# Puzzle-EMG_Sensor_v1_0.net
KiCad netlist of a schematic drawn in EAGLE
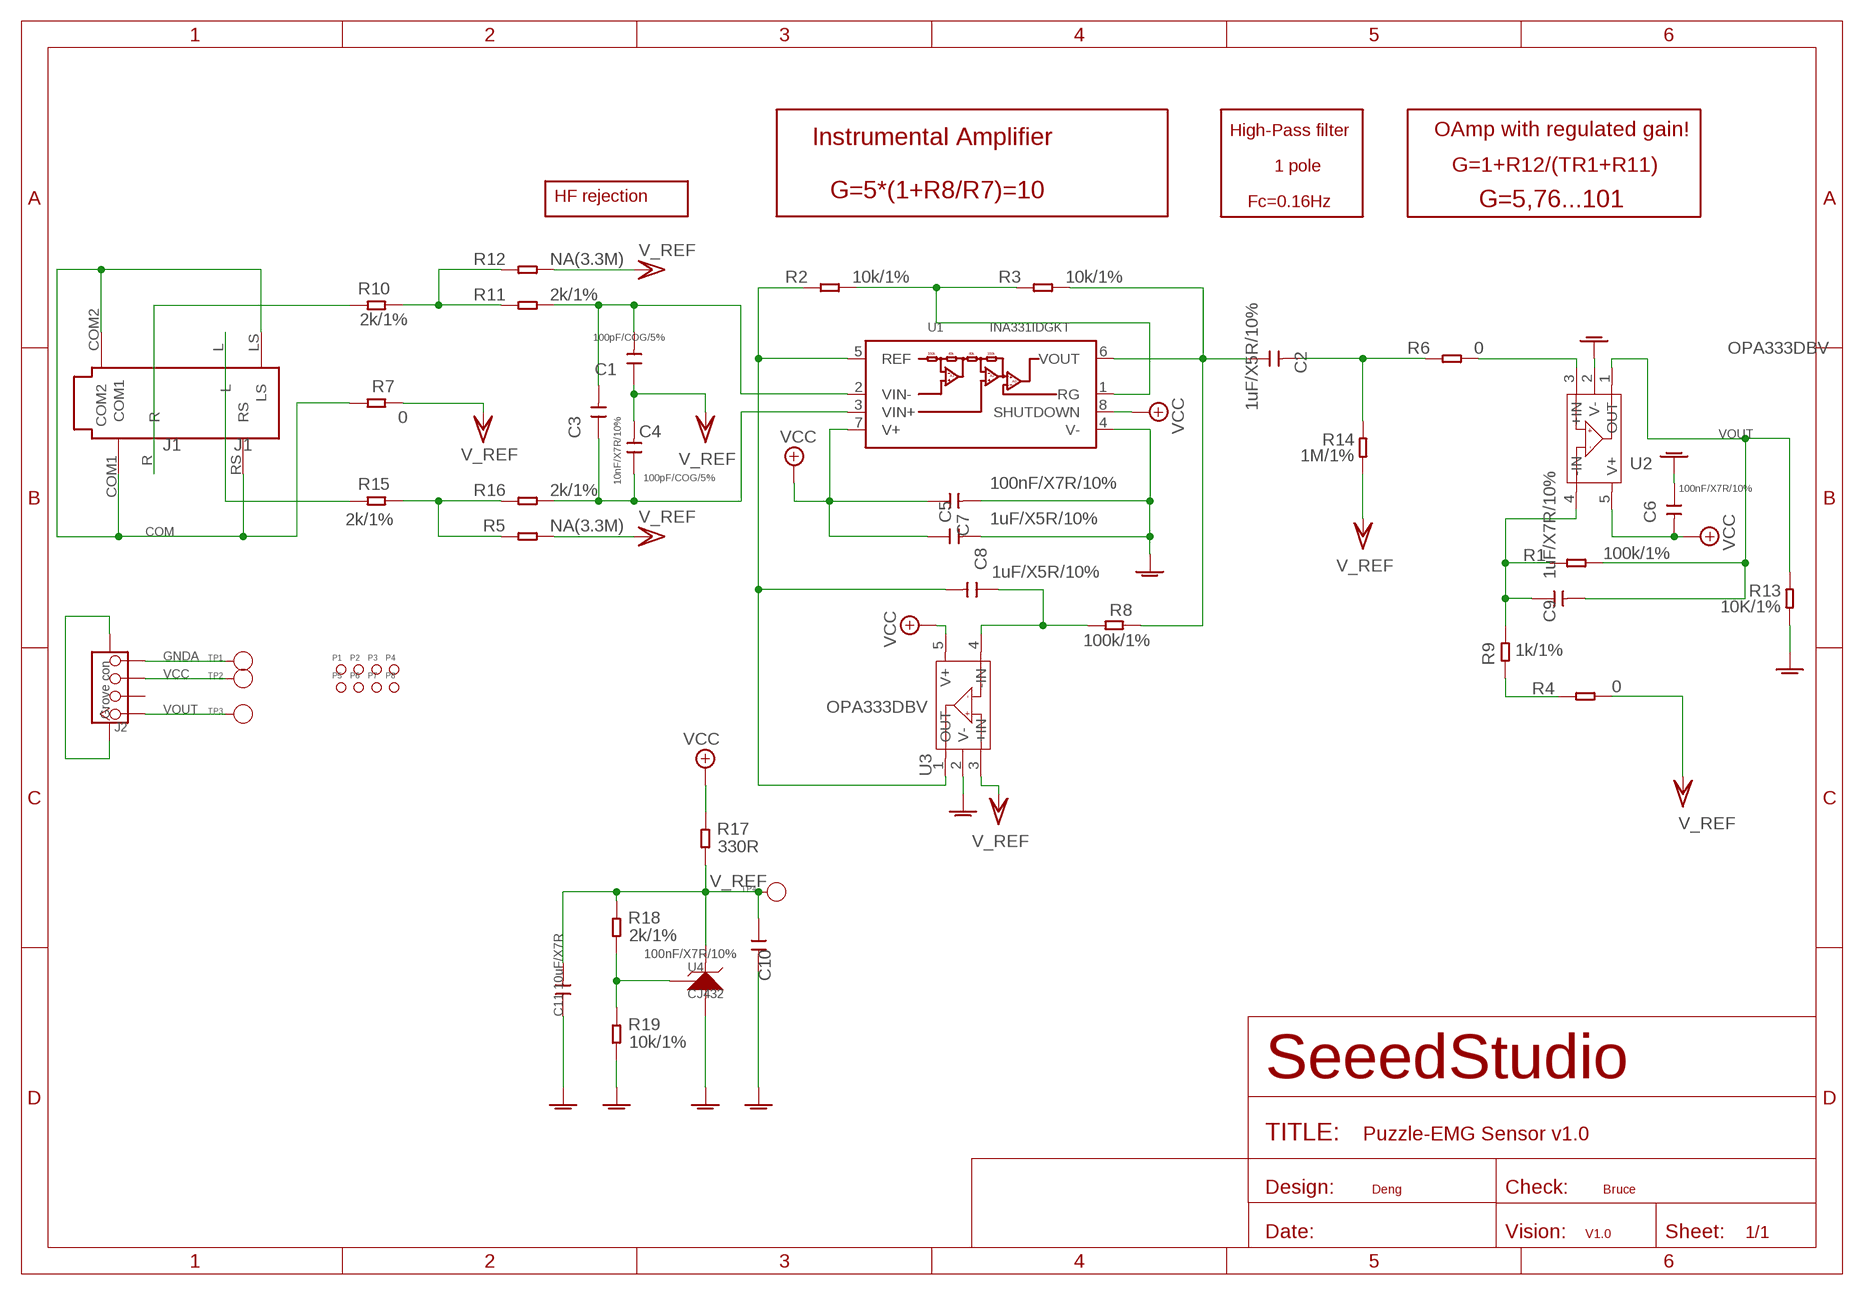
[diagram p0: schematic, sheet 1]

(export (version "E")
  (design (tool "Eeschema 10.0.6"))
  (components
    (comp (ref "C1")
      (value "100pF/COG/5%")
      (footprint "eagle-import:C0603")
      (libsource (lib "eagle-import") (part "C-0603"))
    )
    (comp (ref "C2")
      (value "1uF/X5R/10%")
      (footprint "eagle-import:C0603")
      (libsource (lib "eagle-import") (part "C-0603"))
    )
    (comp (ref "C3")
      (value "10nF/X7R/10%")
      (footprint "eagle-import:C0603")
      (libsource (lib "eagle-import") (part "C-0603"))
    )
    (comp (ref "C4")
      (value "100pF/COG/5%")
      (footprint "eagle-import:C0603")
      (libsource (lib "eagle-import") (part "C-0603"))
    )
    (comp (ref "C5")
      (value "100nF/X7R/10%")
      (footprint "eagle-import:C0603")
      (libsource (lib "eagle-import") (part "C-0603"))
    )
    (comp (ref "C6")
      (value "100nF/X7R/10%")
      (footprint "eagle-import:C0603")
      (libsource (lib "eagle-import") (part "C-0603"))
    )
    (comp (ref "C7")
      (value "1uF/X5R/10%")
      (footprint "eagle-import:C0603")
      (libsource (lib "eagle-import") (part "C-0603"))
    )
    (comp (ref "C8")
      (value "1uF/X5R/10%")
      (footprint "eagle-import:C0603")
      (libsource (lib "eagle-import") (part "C-0603"))
    )
    (comp (ref "C9")
      (value "1uF/X7R/10%")
      (footprint "eagle-import:C0603")
      (libsource (lib "eagle-import") (part "C-0603"))
    )
    (comp (ref "C10")
      (value "100nF/X7R/10%")
      (footprint "eagle-import:C0603")
      (libsource (lib "eagle-import") (part "C-0603"))
    )
    (comp (ref "C11")
      (value "10uF/X7R")
      (footprint "eagle-import:C0805")
      (libsource (lib "eagle-import") (part "C-0805"))
    )
    (comp (ref "J1")
      (value "J1")
      (footprint "eagle-import:6P-SMD-3.5-NEW")
      (libsource (lib "eagle-import") (part "AUDIO-6P-SMD"))
    )
    (comp (ref "J2")
      (value "Grove con")
      (footprint "eagle-import:4P-SMD-2.0")
      (libsource (lib "eagle-import") (part "TWIG-4P-2.0-SMD-FEMALE-REINFORCE'DD'"))
    )
    (comp (ref "P1")
      (value "PAD-MARK")
      (footprint "eagle-import:ROUND-MARK-1.0")
      (fields (field (name "PARTNO") "DNP"))
      (libsource (lib "eagle-import") (part "PAD-MARK"))
    )
    (comp (ref "P2")
      (value "PAD-MARK")
      (footprint "eagle-import:ROUND-MARK-1.0")
      (fields (field (name "PARTNO") "DNP"))
      (libsource (lib "eagle-import") (part "PAD-MARK"))
    )
    (comp (ref "P3")
      (value "PAD-MARK")
      (footprint "eagle-import:ROUND-MARK-1.0")
      (fields (field (name "PARTNO") "DNP"))
      (libsource (lib "eagle-import") (part "PAD-MARK"))
    )
    (comp (ref "P4")
      (value "PAD-MARK")
      (footprint "eagle-import:ROUND-MARK-1.0")
      (fields (field (name "PARTNO") "DNP"))
      (libsource (lib "eagle-import") (part "PAD-MARK"))
    )
    (comp (ref "P5")
      (value "PAD-MARK")
      (footprint "eagle-import:ROUND-MARK-1.0")
      (fields (field (name "PARTNO") "DNP"))
      (libsource (lib "eagle-import") (part "PAD-MARK"))
    )
    (comp (ref "P6")
      (value "PAD-MARK")
      (footprint "eagle-import:ROUND-MARK-1.0")
      (fields (field (name "PARTNO") "DNP"))
      (libsource (lib "eagle-import") (part "PAD-MARK"))
    )
    (comp (ref "P7")
      (value "PAD-MARK")
      (footprint "eagle-import:ROUND-MARK-1.0")
      (fields (field (name "PARTNO") "DNP"))
      (libsource (lib "eagle-import") (part "PAD-MARK"))
    )
    (comp (ref "P8")
      (value "PAD-MARK")
      (footprint "eagle-import:ROUND-MARK-1.0")
      (fields (field (name "PARTNO") "DNP"))
      (libsource (lib "eagle-import") (part "PAD-MARK"))
    )
    (comp (ref "R1")
      (value "100k/1%")
      (footprint "eagle-import:R0603")
      (libsource (lib "eagle-import") (part "R-0603"))
    )
    (comp (ref "R2")
      (value "10k/1%")
      (footprint "eagle-import:R0603")
      (libsource (lib "eagle-import") (part "R-0603"))
    )
    (comp (ref "R3")
      (value "10k/1%")
      (footprint "eagle-import:R0603")
      (libsource (lib "eagle-import") (part "R-0603"))
    )
    (comp (ref "R4")
      (value "0")
      (footprint "eagle-import:R0603")
      (libsource (lib "eagle-import") (part "R-0603"))
    )
    (comp (ref "R5")
      (value "NA(3.3M)")
      (footprint "eagle-import:R0603")
      (libsource (lib "eagle-import") (part "R-0603"))
    )
    (comp (ref "R6")
      (value "0")
      (footprint "eagle-import:R0603")
      (libsource (lib "eagle-import") (part "R-0603"))
    )
    (comp (ref "R7")
      (value "0")
      (footprint "eagle-import:R0603")
      (libsource (lib "eagle-import") (part "R-0603"))
    )
    (comp (ref "R8")
      (value "100k/1%")
      (footprint "eagle-import:R0603")
      (libsource (lib "eagle-import") (part "R-0603"))
    )
    (comp (ref "R9")
      (value "1k/1%")
      (footprint "eagle-import:R0603")
      (libsource (lib "eagle-import") (part "R-0603"))
    )
    (comp (ref "R10")
      (value "2k/1%")
      (footprint "eagle-import:R0603")
      (libsource (lib "eagle-import") (part "R-0603"))
    )
    (comp (ref "R11")
      (value "2k/1%")
      (footprint "eagle-import:R0603")
      (libsource (lib "eagle-import") (part "R-0603"))
    )
    (comp (ref "R12")
      (value "NA(3.3M)")
      (footprint "eagle-import:R0603")
      (libsource (lib "eagle-import") (part "R-0603"))
    )
    (comp (ref "R13")
      (value "10K/1%")
      (footprint "eagle-import:R0603")
      (libsource (lib "eagle-import") (part "R-0603"))
    )
    (comp (ref "R14")
      (value "1M/1%")
      (footprint "eagle-import:R0603")
      (libsource (lib "eagle-import") (part "R-0603"))
    )
    (comp (ref "R15")
      (value "2k/1%")
      (footprint "eagle-import:R0603")
      (libsource (lib "eagle-import") (part "R-0603"))
    )
    (comp (ref "R16")
      (value "2k/1%")
      (footprint "eagle-import:R0603")
      (libsource (lib "eagle-import") (part "R-0603"))
    )
    (comp (ref "R17")
      (value "330R")
      (footprint "eagle-import:R0603")
      (libsource (lib "eagle-import") (part "R-0603"))
    )
    (comp (ref "R18")
      (value "2k/1%")
      (footprint "eagle-import:R0603")
      (libsource (lib "eagle-import") (part "R-0603"))
    )
    (comp (ref "R19")
      (value "10k/1%")
      (footprint "eagle-import:R0603")
      (libsource (lib "eagle-import") (part "R-0603"))
    )
    (comp (ref "TP1")
      (value "TP1")
      (footprint "eagle-import:TP_4545")
      (fields (field (name "PARTNO") "DNP"))
      (libsource (lib "eagle-import") (part "PAD-TEST-POINT'4545'"))
    )
    (comp (ref "TP2")
      (value "TP2")
      (footprint "eagle-import:TP_4545")
      (fields (field (name "PARTNO") "DNP"))
      (libsource (lib "eagle-import") (part "PAD-TEST-POINT'4545'"))
    )
    (comp (ref "TP3")
      (value "TP3")
      (footprint "eagle-import:TP_4545")
      (fields (field (name "PARTNO") "DNP"))
      (libsource (lib "eagle-import") (part "PAD-TEST-POINT'4545'"))
    )
    (comp (ref "TP4")
      (value "TP4")
      (footprint "eagle-import:TP_4545")
      (fields (field (name "PARTNO") "DNP"))
      (libsource (lib "eagle-import") (part "PAD-TEST-POINT'4545'"))
    )
    (comp (ref "U1")
      (value "INA331IDGKT")
      (footprint "eagle-import:MSOP-8")
      (libsource (lib "eagle-import") (part "INA331EA"))
    )
    (comp (ref "U2")
      (value "OPA333DBV")
      (footprint "eagle-import:SOT23-5")
      (libsource (lib "eagle-import") (part "OPA333DBV"))
    )
    (comp (ref "U3")
      (value "OPA333DBV")
      (footprint "eagle-import:SOT23-5")
      (libsource (lib "eagle-import") (part "OPA333DBV"))
    )
    (comp (ref "U4")
      (value "CJ432")
      (footprint "eagle-import:SOT23")
      (libsource (lib "eagle-import") (part "REFERENCE-SOURCE"))
    )
  )
  (nets
    (net (code "1") (name "/COM") (class "Default")
      (node (ref "J1") (pin "COM1") (pinfunction "COM1_COM1") (pintype "bidirectional"))
      (node (ref "J1") (pin "COM2") (pinfunction "COM2_COM2") (pintype "bidirectional"))
      (node (ref "J1") (pin "LS") (pinfunction "LS_LS") (pintype "bidirectional"))
      (node (ref "J1") (pin "RS") (pinfunction "RS_RS") (pintype "bidirectional"))
      (node (ref "R7") (pin "1") (pinfunction "1_1") (pintype "passive"))
    )
    (net (code "2") (name "/VOUT") (class "Default")
      (node (ref "C9") (pin "2") (pinfunction "2_2") (pintype "passive"))
      (node (ref "J2") (pin "1") (pinfunction "1_1") (pintype "bidirectional"))
      (node (ref "R1") (pin "2") (pinfunction "2_2") (pintype "passive"))
      (node (ref "R13") (pin "1") (pinfunction "1_1") (pintype "passive"))
      (node (ref "TP3") (pin "T") (pinfunction "T_T") (pintype "bidirectional"))
      (node (ref "U2") (pin "1") (pinfunction "OUT_1") (pintype "bidirectional"))
    )
    (net (code "3") (name "GNDA") (class "Default")
      (node (ref "C10") (pin "2") (pinfunction "2_2") (pintype "passive"))
      (node (ref "C11") (pin "1") (pinfunction "1_1") (pintype "passive"))
      (node (ref "C5") (pin "2") (pinfunction "2_2") (pintype "passive"))
      (node (ref "C6") (pin "1") (pinfunction "1_1") (pintype "passive"))
      (node (ref "C7") (pin "2") (pinfunction "2_2") (pintype "passive"))
      (node (ref "J2") (pin "4") (pinfunction "4_4") (pintype "bidirectional"))
      (node (ref "R13") (pin "2") (pinfunction "2_2") (pintype "passive"))
      (node (ref "R19") (pin "1") (pinfunction "1_1") (pintype "passive"))
      (node (ref "TP1") (pin "T") (pinfunction "T_T") (pintype "bidirectional"))
      (node (ref "U1") (pin "4") (pinfunction "V-_4") (pintype "power_in"))
      (node (ref "U2") (pin "2") (pinfunction "V-_2") (pintype "bidirectional"))
      (node (ref "U3") (pin "2") (pinfunction "V-_2") (pintype "bidirectional"))
      (node (ref "U4") (pin "3") (pinfunction "A_3") (pintype "bidirectional"))
    )
    (net (code "4") (name "Net-(C2-Pad2)") (class "Default")
      (node (ref "C2") (pin "2") (pinfunction "2_2") (pintype "passive"))
      (node (ref "R14") (pin "1") (pinfunction "1_1") (pintype "passive"))
      (node (ref "R6") (pin "2") (pinfunction "2_2") (pintype "passive"))
    )
    (net (code "5") (name "Net-(J1-PadL)") (class "Default")
      (node (ref "J1") (pin "L") (pinfunction "L_L") (pintype "bidirectional"))
      (node (ref "R15") (pin "1") (pinfunction "1_1") (pintype "passive"))
    )
    (net (code "6") (name "Net-(J1-PadR)") (class "Default")
      (node (ref "J1") (pin "R") (pinfunction "R_R") (pintype "bidirectional"))
      (node (ref "R10") (pin "1") (pinfunction "1_1") (pintype "passive"))
    )
    (net (code "7") (name "Net-(R4-Pad1)") (class "Default")
      (node (ref "R4") (pin "1") (pinfunction "1_1") (pintype "passive"))
      (node (ref "R9") (pin "2") (pinfunction "2_2") (pintype "passive"))
    )
    (net (code "8") (name "Net-(R10-Pad2)") (class "Default")
      (node (ref "R10") (pin "2") (pinfunction "2_2") (pintype "passive"))
      (node (ref "R11") (pin "2") (pinfunction "2_2") (pintype "passive"))
      (node (ref "R12") (pin "2") (pinfunction "2_2") (pintype "passive"))
    )
    (net (code "9") (name "Net-(R15-Pad2)") (class "Default")
      (node (ref "R15") (pin "2") (pinfunction "2_2") (pintype "passive"))
      (node (ref "R16") (pin "2") (pinfunction "2_2") (pintype "passive"))
      (node (ref "R5") (pin "2") (pinfunction "2_2") (pintype "passive"))
    )
    (net (code "10") (name "Net-(U1-REF)") (class "Default")
      (node (ref "C8") (pin "2") (pinfunction "2_2") (pintype "passive"))
      (node (ref "R2") (pin "2") (pinfunction "2_2") (pintype "passive"))
      (node (ref "U1") (pin "5") (pinfunction "REF_5") (pintype "input"))
      (node (ref "U3") (pin "1") (pinfunction "OUT_1") (pintype "bidirectional"))
    )
    (net (code "11") (name "Net-(U1-RG)") (class "Default")
      (node (ref "R2") (pin "1") (pinfunction "1_1") (pintype "passive"))
      (node (ref "R3") (pin "2") (pinfunction "2_2") (pintype "passive"))
      (node (ref "U1") (pin "1") (pinfunction "RG_1") (pintype "input"))
    )
    (net (code "12") (name "Net-(U1-VIN+)") (class "Default")
      (node (ref "C3") (pin "1") (pinfunction "1_1") (pintype "passive"))
      (node (ref "C4") (pin "1") (pinfunction "1_1") (pintype "passive"))
      (node (ref "R16") (pin "1") (pinfunction "1_1") (pintype "passive"))
      (node (ref "U1") (pin "3") (pinfunction "VIN+_3") (pintype "input"))
    )
    (net (code "13") (name "Net-(U1-VIN-)") (class "Default")
      (node (ref "C1") (pin "2") (pinfunction "2_2") (pintype "passive"))
      (node (ref "C3") (pin "2") (pinfunction "2_2") (pintype "passive"))
      (node (ref "R11") (pin "1") (pinfunction "1_1") (pintype "passive"))
      (node (ref "U1") (pin "2") (pinfunction "VIN-_2") (pintype "input"))
    )
    (net (code "14") (name "Net-(U1-VOUT)") (class "Default")
      (node (ref "C2") (pin "1") (pinfunction "1_1") (pintype "passive"))
      (node (ref "R3") (pin "1") (pinfunction "1_1") (pintype "passive"))
      (node (ref "R8") (pin "2") (pinfunction "2_2") (pintype "passive"))
      (node (ref "U1") (pin "6") (pinfunction "VOUT_6") (pintype "output"))
    )
    (net (code "15") (name "Net-(U2-+IN)") (class "Default")
      (node (ref "R6") (pin "1") (pinfunction "1_1") (pintype "passive"))
      (node (ref "U2") (pin "3") (pinfunction "+IN_3") (pintype "bidirectional"))
    )
    (net (code "16") (name "Net-(U2--IN)") (class "Default")
      (node (ref "C9") (pin "1") (pinfunction "1_1") (pintype "passive"))
      (node (ref "R1") (pin "1") (pinfunction "1_1") (pintype "passive"))
      (node (ref "R9") (pin "1") (pinfunction "1_1") (pintype "passive"))
      (node (ref "U2") (pin "4") (pinfunction "-IN_4") (pintype "bidirectional"))
    )
    (net (code "17") (name "Net-(U3--IN)") (class "Default")
      (node (ref "C8") (pin "1") (pinfunction "1_1") (pintype "passive"))
      (node (ref "R8") (pin "1") (pinfunction "1_1") (pintype "passive"))
      (node (ref "U3") (pin "4") (pinfunction "-IN_4") (pintype "bidirectional"))
    )
    (net (code "18") (name "Net-(U4-R)") (class "Default")
      (node (ref "R18") (pin "1") (pinfunction "1_1") (pintype "passive"))
      (node (ref "R19") (pin "2") (pinfunction "2_2") (pintype "passive"))
      (node (ref "U4") (pin "1") (pinfunction "R_1") (pintype "bidirectional"))
    )
    (net (code "19") (name "VCC") (class "Default")
      (node (ref "C5") (pin "1") (pinfunction "1_1") (pintype "passive"))
      (node (ref "C6") (pin "2") (pinfunction "2_2") (pintype "passive"))
      (node (ref "C7") (pin "1") (pinfunction "1_1") (pintype "passive"))
      (node (ref "J2") (pin "3") (pinfunction "3_3") (pintype "bidirectional"))
      (node (ref "R17") (pin "2") (pinfunction "2_2") (pintype "passive"))
      (node (ref "TP2") (pin "T") (pinfunction "T_T") (pintype "bidirectional"))
      (node (ref "U1") (pin "7") (pinfunction "V+_7") (pintype "power_in"))
      (node (ref "U1") (pin "8") (pinfunction "SHUTDOWN_8") (pintype "input"))
      (node (ref "U2") (pin "5") (pinfunction "V+_5") (pintype "bidirectional"))
      (node (ref "U3") (pin "5") (pinfunction "V+_5") (pintype "bidirectional"))
    )
    (net (code "20") (name "V_REF") (class "Default")
      (node (ref "C1") (pin "1") (pinfunction "1_1") (pintype "passive"))
      (node (ref "C10") (pin "1") (pinfunction "1_1") (pintype "passive"))
      (node (ref "C11") (pin "2") (pinfunction "2_2") (pintype "passive"))
      (node (ref "C4") (pin "2") (pinfunction "2_2") (pintype "passive"))
      (node (ref "J2") (pin "SS1") (pinfunction "SS1_SS1") (pintype "bidirectional"))
      (node (ref "J2") (pin "SS2") (pinfunction "SS2_SS2") (pintype "bidirectional"))
      (node (ref "R12") (pin "1") (pinfunction "1_1") (pintype "passive"))
      (node (ref "R14") (pin "2") (pinfunction "2_2") (pintype "passive"))
      (node (ref "R17") (pin "1") (pinfunction "1_1") (pintype "passive"))
      (node (ref "R18") (pin "2") (pinfunction "2_2") (pintype "passive"))
      (node (ref "R4") (pin "2") (pinfunction "2_2") (pintype "passive"))
      (node (ref "R5") (pin "1") (pinfunction "1_1") (pintype "passive"))
      (node (ref "R7") (pin "2") (pinfunction "2_2") (pintype "passive"))
      (node (ref "TP4") (pin "T") (pinfunction "T_T") (pintype "bidirectional"))
      (node (ref "U3") (pin "3") (pinfunction "+IN_3") (pintype "bidirectional"))
      (node (ref "U4") (pin "2") (pinfunction "K_2") (pintype "bidirectional"))
    )
    (net (code "21") (name "unconnected-(J2-Pad2)") (class "Default")
      (node (ref "J2") (pin "2") (pinfunction "2_2") (pintype "bidirectional"))
    )
  )
)
